# Si4703_Eval.net
KiCad netlist of a schematic drawn in EAGLE
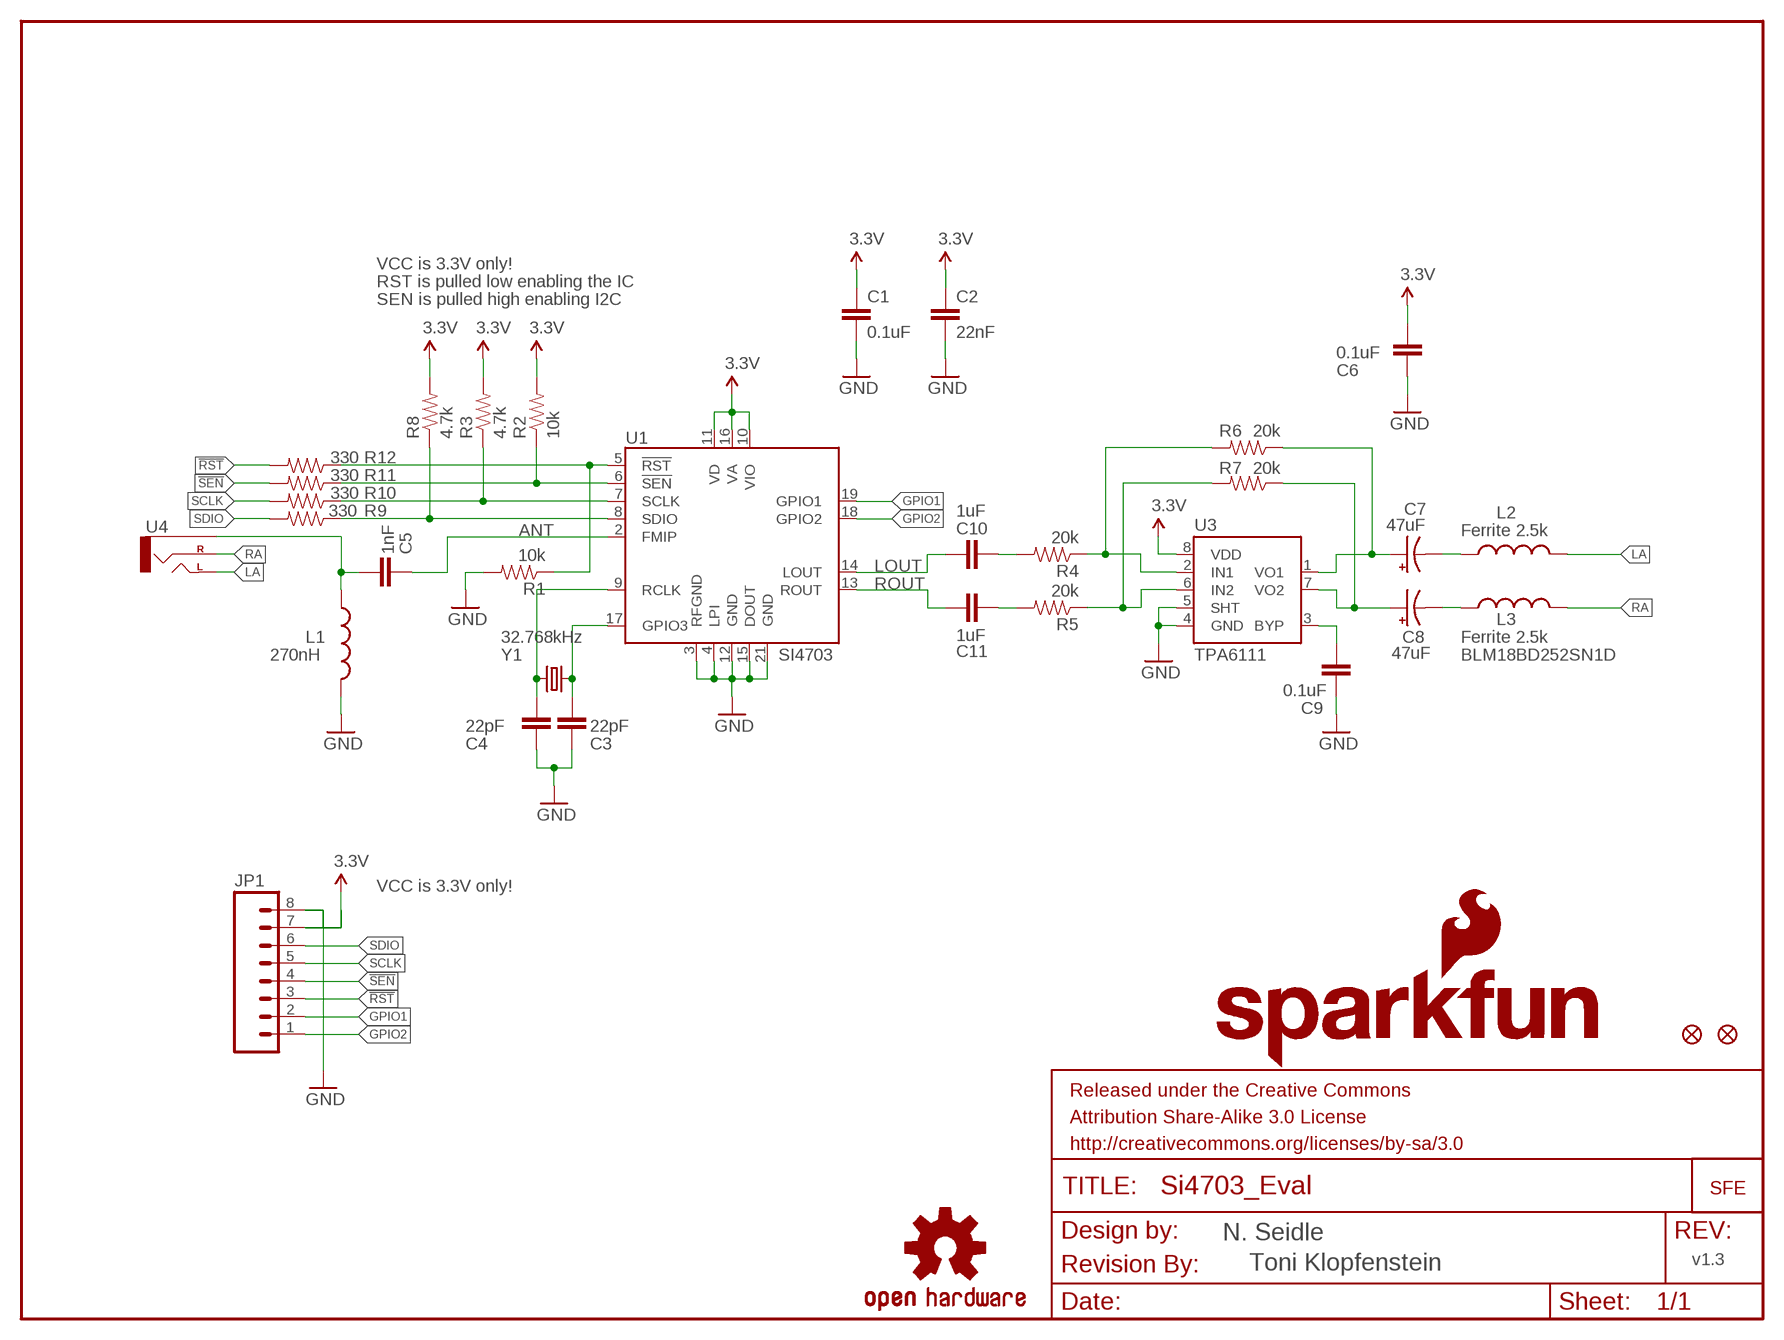
[diagram p0: schematic, sheet 1]

(export (version "E")
  (design (tool "Eeschema 10.0.6"))
  (components
    (comp (ref "C1")
      (value "0.1uF")
      (footprint "eagle-import:0603-CAP")
      (libsource (lib "eagle-import") (part "0.1UF-25V(+80/-20%)(0603)"))
    )
    (comp (ref "C2")
      (value "22nF")
      (footprint "eagle-import:0603-CAP")
      (libsource (lib "eagle-import") (part "22NF/22,000PF-50V-10%(0603)"))
    )
    (comp (ref "C3")
      (value "22pF")
      (footprint "eagle-import:0603-CAP")
      (libsource (lib "eagle-import") (part "22PF-50V-5%(0603)"))
    )
    (comp (ref "C4")
      (value "22pF")
      (footprint "eagle-import:0603-CAP")
      (libsource (lib "eagle-import") (part "22PF-50V-5%(0603)"))
    )
    (comp (ref "C5")
      (value "1nF")
      (footprint "eagle-import:0603-CAP")
      (libsource (lib "eagle-import") (part "1NF/1000PF-50V-10%(0603)"))
    )
    (comp (ref "C6")
      (value "0.1uF")
      (footprint "eagle-import:0603-CAP")
      (libsource (lib "eagle-import") (part "0.1UF-25V(+80/-20%)(0603)"))
    )
    (comp (ref "C7")
      (value "47uF")
      (footprint "eagle-import:EIA3528")
      (libsource (lib "eagle-import") (part "47UF-TANT"))
    )
    (comp (ref "C8")
      (value "47uF")
      (footprint "eagle-import:EIA3528")
      (libsource (lib "eagle-import") (part "47UF-TANT"))
    )
    (comp (ref "C9")
      (value "0.1uF")
      (footprint "eagle-import:0603-CAP")
      (libsource (lib "eagle-import") (part "0.1UF-25V(+80/-20%)(0603)"))
    )
    (comp (ref "C10")
      (value "1uF")
      (footprint "eagle-import:0603-CAP")
      (libsource (lib "eagle-import") (part "1.0UF-16V-10%(0603)"))
    )
    (comp (ref "C11")
      (value "1uF")
      (footprint "eagle-import:0603-CAP")
      (libsource (lib "eagle-import") (part "1.0UF-16V-10%(0603)"))
    )
    (comp (ref "FRAME2")
      (value "FRAME-LETTER")
      (footprint "eagle-import:CREATIVE_COMMONS")
      (libsource (lib "eagle-import") (part "FRAME-LETTER"))
    )
    (comp (ref "JP1")
      (value "M08")
      (footprint "eagle-import:1X08")
      (libsource (lib "eagle-import") (part "M08"))
    )
    (comp (ref "JP3")
      (value "LOGO-SFESK")
      (footprint "eagle-import:SFE-LOGO-FLAME")
      (libsource (lib "eagle-import") (part "LOGO-SFESK"))
    )
    (comp (ref "JP4")
      (value "FIDUCIAL1X2")
      (footprint "eagle-import:FIDUCIAL-1X2")
      (libsource (lib "eagle-import") (part "FIDUCIAL1X2"))
    )
    (comp (ref "JP5")
      (value "FIDUCIAL1X2")
      (footprint "eagle-import:FIDUCIAL-1X2")
      (libsource (lib "eagle-import") (part "FIDUCIAL1X2"))
    )
    (comp (ref "L1")
      (value "270nH")
      (footprint "eagle-import:0603")
      (libsource (lib "eagle-import") (part "INDUCTOR0603"))
    )
    (comp (ref "L2")
      (value "Ferrite 2.5k")
      (footprint "eagle-import:0603")
      (libsource (lib "eagle-import") (part "INDUCTOR0603"))
    )
    (comp (ref "L3")
      (value "Ferrite 2.5k")
      (footprint "eagle-import:0603")
      (libsource (lib "eagle-import") (part "INDUCTOR0603"))
    )
    (comp (ref "LOGO1")
      (value "SFE_LOGO_NAME_FLAME.1_INCH")
      (footprint "eagle-import:SFE_LOGO_NAME_FLAME_.1")
      (libsource (lib "eagle-import") (part "SFE_LOGO_NAME_FLAME.1_INCH"))
    )
    (comp (ref "LOGO2")
      (value "OSHW-LOGOS")
      (footprint "eagle-import:OSHW-LOGO-S")
      (libsource (lib "eagle-import") (part "OSHW-LOGOS"))
    )
    (comp (ref "R1")
      (value "10k")
      (footprint "eagle-import:0603-RES")
      (libsource (lib "eagle-import") (part "10KOHM1/10W1%(0603)0603"))
    )
    (comp (ref "R2")
      (value "10k")
      (footprint "eagle-import:0603-RES")
      (libsource (lib "eagle-import") (part "10KOHM1/10W1%(0603)0603"))
    )
    (comp (ref "R3")
      (value "4.7k")
      (footprint "eagle-import:0603")
      (libsource (lib "eagle-import") (part "4.7KOHM1/10W1%(0603)"))
    )
    (comp (ref "R4")
      (value "20k")
      (footprint "eagle-import:0603-RES")
      (libsource (lib "eagle-import") (part "20KOHM1/10W1%(0603)"))
    )
    (comp (ref "R5")
      (value "20k")
      (footprint "eagle-import:0603-RES")
      (libsource (lib "eagle-import") (part "20KOHM1/10W1%(0603)"))
    )
    (comp (ref "R6")
      (value "20k")
      (footprint "eagle-import:0603-RES")
      (libsource (lib "eagle-import") (part "20KOHM1/10W1%(0603)"))
    )
    (comp (ref "R7")
      (value "20k")
      (footprint "eagle-import:0603-RES")
      (libsource (lib "eagle-import") (part "20KOHM1/10W1%(0603)"))
    )
    (comp (ref "R8")
      (value "4.7k")
      (footprint "eagle-import:0603")
      (libsource (lib "eagle-import") (part "4.7KOHM1/10W1%(0603)"))
    )
    (comp (ref "R9")
      (value "330")
      (footprint "eagle-import:0603-RES")
      (libsource (lib "eagle-import") (part "330OHM1/10W1%(0603)"))
    )
    (comp (ref "R10")
      (value "330")
      (footprint "eagle-import:0603-RES")
      (libsource (lib "eagle-import") (part "330OHM1/10W1%(0603)"))
    )
    (comp (ref "R11")
      (value "330")
      (footprint "eagle-import:0603-RES")
      (libsource (lib "eagle-import") (part "330OHM1/10W1%(0603)"))
    )
    (comp (ref "R12")
      (value "330")
      (footprint "eagle-import:0603-RES")
      (libsource (lib "eagle-import") (part "330OHM1/10W1%(0603)"))
    )
    (comp (ref "U$1")
      (value "REVISION")
      (footprint "eagle-import:REVISION")
      (libsource (lib "eagle-import") (part "REVISION"))
    )
    (comp (ref "U1")
      (value "SI4703")
      (footprint "eagle-import:SI470X")
      (libsource (lib "eagle-import") (part "SI470X"))
    )
    (comp (ref "U3")
      (value "TPA6111")
      (footprint "eagle-import:SO08-TIGHT")
      (libsource (lib "eagle-import") (part "TPA6111SMD-T"))
    )
    (comp (ref "U4")
      (value "AUDIO-JACKSMD2")
      (footprint "eagle-import:AUDIO-JACK-3.5MM-SMD")
      (libsource (lib "eagle-import") (part "AUDIO-JACKSMD2"))
    )
    (comp (ref "Y1")
      (value "32.768kHz")
      (footprint "eagle-import:CRYSTAL-32KHZ-SMD")
      (libsource (lib "eagle-import") (part "CRYSTAL32-SMD"))
    )
  )
  (nets
    (net (code "1") (name "/ANT") (class "Default")
      (node (ref "C5") (pin "1") (pinfunction "1_1") (pintype "passive"))
      (node (ref "U1") (pin "2") (pinfunction "FMIP_2") (pintype "bidirectional"))
    )
    (net (code "2") (name "/LOUT") (class "Default")
      (node (ref "C10") (pin "1") (pinfunction "1_1") (pintype "passive"))
      (node (ref "U1") (pin "14") (pinfunction "LOUT_14") (pintype "bidirectional"))
    )
    (net (code "3") (name "/ROUT") (class "Default")
      (node (ref "C11") (pin "1") (pinfunction "1_1") (pintype "passive"))
      (node (ref "U1") (pin "13") (pinfunction "ROUT_13") (pintype "bidirectional"))
    )
    (net (code "4") (name "/~{RST}") (class "Default")
      (node (ref "JP1") (pin "3") (pinfunction "3_3") (pintype "passive"))
      (node (ref "R12") (pin "2") (pinfunction "2_2") (pintype "passive"))
    )
    (net (code "5") (name "/~{SEN}") (class "Default")
      (node (ref "JP1") (pin "4") (pinfunction "4_4") (pintype "passive"))
      (node (ref "R11") (pin "2") (pinfunction "2_2") (pintype "passive"))
    )
    (net (code "6") (name "3.3V") (class "Default")
      (node (ref "C1") (pin "1") (pinfunction "1_1") (pintype "passive"))
      (node (ref "C2") (pin "1") (pinfunction "1_1") (pintype "passive"))
      (node (ref "C6") (pin "2") (pinfunction "2_2") (pintype "passive"))
      (node (ref "JP1") (pin "7") (pinfunction "7_7") (pintype "passive"))
      (node (ref "R2") (pin "2") (pinfunction "2_2") (pintype "passive"))
      (node (ref "R3") (pin "2") (pinfunction "2_2") (pintype "passive"))
      (node (ref "R8") (pin "2") (pinfunction "2_2") (pintype "passive"))
      (node (ref "U1") (pin "10") (pinfunction "VIO_10") (pintype "bidirectional"))
      (node (ref "U1") (pin "11") (pinfunction "VD_11") (pintype "bidirectional"))
      (node (ref "U1") (pin "16") (pinfunction "VA_16") (pintype "bidirectional"))
      (node (ref "U3") (pin "8") (pinfunction "VDD_8") (pintype "bidirectional"))
    )
    (net (code "7") (name "GND") (class "Default")
      (node (ref "C1") (pin "2") (pinfunction "2_2") (pintype "passive"))
      (node (ref "C2") (pin "2") (pinfunction "2_2") (pintype "passive"))
      (node (ref "C3") (pin "1") (pinfunction "1_1") (pintype "passive"))
      (node (ref "C4") (pin "1") (pinfunction "1_1") (pintype "passive"))
      (node (ref "C6") (pin "1") (pinfunction "1_1") (pintype "passive"))
      (node (ref "C9") (pin "2") (pinfunction "2_2") (pintype "passive"))
      (node (ref "JP1") (pin "8") (pinfunction "8_8") (pintype "passive"))
      (node (ref "L1") (pin "2") (pinfunction "2_2") (pintype "passive"))
      (node (ref "R1") (pin "2") (pinfunction "2_2") (pintype "passive"))
      (node (ref "U1") (pin "12") (pinfunction "GND_12") (pintype "bidirectional"))
      (node (ref "U1") (pin "15") (pinfunction "DOUT_15") (pintype "bidirectional"))
      (node (ref "U1") (pin "21") (pinfunction "GND_21") (pintype "bidirectional"))
      (node (ref "U1") (pin "3") (pinfunction "RFGND_3") (pintype "bidirectional"))
      (node (ref "U1") (pin "4") (pinfunction "LPI_4") (pintype "bidirectional"))
      (node (ref "U3") (pin "4") (pinfunction "GND_4") (pintype "bidirectional"))
      (node (ref "U3") (pin "5") (pinfunction "SHT_5") (pintype "bidirectional"))
    )
    (net (code "8") (name "GPIO1") (class "Default")
      (node (ref "JP1") (pin "2") (pinfunction "2_2") (pintype "passive"))
      (node (ref "U1") (pin "19") (pinfunction "GPIO1_19") (pintype "bidirectional"))
    )
    (net (code "9") (name "GPIO2") (class "Default")
      (node (ref "JP1") (pin "1") (pinfunction "1_1") (pintype "passive"))
      (node (ref "U1") (pin "18") (pinfunction "GPIO2_18") (pintype "bidirectional"))
    )
    (net (code "10") (name "LA") (class "Default")
      (node (ref "L2") (pin "2") (pinfunction "2_2") (pintype "passive"))
      (node (ref "U4") (pin "TIP") (pinfunction "LEFT_TIP") (pintype "bidirectional"))
    )
    (net (code "11") (name "Net-(C5-Pad2)") (class "Default")
      (node (ref "C5") (pin "2") (pinfunction "2_2") (pintype "passive"))
      (node (ref "L1") (pin "1") (pinfunction "1_1") (pintype "passive"))
      (node (ref "U4") (pin "SLEEVE") (pinfunction "SLEEVE_SLEEVE") (pintype "bidirectional"))
    )
    (net (code "12") (name "Net-(C7-+)") (class "Default")
      (node (ref "C7") (pin "A") (pinfunction "+_A") (pintype "passive"))
      (node (ref "R6") (pin "1") (pinfunction "1_1") (pintype "passive"))
      (node (ref "U3") (pin "1") (pinfunction "VO1_1") (pintype "bidirectional"))
    )
    (net (code "13") (name "Net-(C7--)") (class "Default")
      (node (ref "C7") (pin "C") (pinfunction "-_C") (pintype "passive"))
      (node (ref "L2") (pin "1") (pinfunction "1_1") (pintype "passive"))
    )
    (net (code "14") (name "Net-(C8-+)") (class "Default")
      (node (ref "C8") (pin "A") (pinfunction "+_A") (pintype "passive"))
      (node (ref "R7") (pin "1") (pinfunction "1_1") (pintype "passive"))
      (node (ref "U3") (pin "7") (pinfunction "VO2_7") (pintype "bidirectional"))
    )
    (net (code "15") (name "Net-(C8--)") (class "Default")
      (node (ref "C8") (pin "C") (pinfunction "-_C") (pintype "passive"))
      (node (ref "L3") (pin "1") (pinfunction "1_1") (pintype "passive"))
    )
    (net (code "16") (name "Net-(C10-Pad2)") (class "Default")
      (node (ref "C10") (pin "2") (pinfunction "2_2") (pintype "passive"))
      (node (ref "R4") (pin "2") (pinfunction "2_2") (pintype "passive"))
    )
    (net (code "17") (name "Net-(C11-Pad2)") (class "Default")
      (node (ref "C11") (pin "2") (pinfunction "2_2") (pintype "passive"))
      (node (ref "R5") (pin "2") (pinfunction "2_2") (pintype "passive"))
    )
    (net (code "18") (name "Net-(U1-GPIO3)") (class "Default")
      (node (ref "C3") (pin "2") (pinfunction "2_2") (pintype "passive"))
      (node (ref "U1") (pin "17") (pinfunction "GPIO3_17") (pintype "bidirectional"))
      (node (ref "Y1") (pin "X1") (pinfunction "1_X1") (pintype "passive"))
    )
    (net (code "19") (name "Net-(U1-RCLK)") (class "Default")
      (node (ref "C4") (pin "2") (pinfunction "2_2") (pintype "passive"))
      (node (ref "U1") (pin "9") (pinfunction "RCLK_9") (pintype "bidirectional"))
      (node (ref "Y1") (pin "X2") (pinfunction "2_X2") (pintype "passive"))
    )
    (net (code "20") (name "Net-(U1-SCLK)") (class "Default")
      (node (ref "R10") (pin "1") (pinfunction "1_1") (pintype "passive"))
      (node (ref "R3") (pin "1") (pinfunction "1_1") (pintype "passive"))
      (node (ref "U1") (pin "7") (pinfunction "SCLK_7") (pintype "bidirectional"))
    )
    (net (code "21") (name "Net-(U1-SDIO)") (class "Default")
      (node (ref "R8") (pin "1") (pinfunction "1_1") (pintype "passive"))
      (node (ref "R9") (pin "1") (pinfunction "1_1") (pintype "passive"))
      (node (ref "U1") (pin "8") (pinfunction "SDIO_8") (pintype "bidirectional"))
    )
    (net (code "22") (name "Net-(U1-~{RST})") (class "Default")
      (node (ref "R1") (pin "1") (pinfunction "1_1") (pintype "passive"))
      (node (ref "R12") (pin "1") (pinfunction "1_1") (pintype "passive"))
      (node (ref "U1") (pin "5") (pinfunction "~{RST}_5") (pintype "bidirectional"))
    )
    (net (code "23") (name "Net-(U1-~{SEN})") (class "Default")
      (node (ref "R11") (pin "1") (pinfunction "1_1") (pintype "passive"))
      (node (ref "R2") (pin "1") (pinfunction "1_1") (pintype "passive"))
      (node (ref "U1") (pin "6") (pinfunction "~{SEN}_6") (pintype "bidirectional"))
    )
    (net (code "24") (name "Net-(U3-BYP)") (class "Default")
      (node (ref "C9") (pin "1") (pinfunction "1_1") (pintype "passive"))
      (node (ref "U3") (pin "3") (pinfunction "BYP_3") (pintype "bidirectional"))
    )
    (net (code "25") (name "Net-(U3-IN1)") (class "Default")
      (node (ref "R4") (pin "1") (pinfunction "1_1") (pintype "passive"))
      (node (ref "R6") (pin "2") (pinfunction "2_2") (pintype "passive"))
      (node (ref "U3") (pin "2") (pinfunction "IN1_2") (pintype "bidirectional"))
    )
    (net (code "26") (name "Net-(U3-IN2)") (class "Default")
      (node (ref "R5") (pin "1") (pinfunction "1_1") (pintype "passive"))
      (node (ref "R7") (pin "2") (pinfunction "2_2") (pintype "passive"))
      (node (ref "U3") (pin "6") (pinfunction "IN2_6") (pintype "bidirectional"))
    )
    (net (code "27") (name "RA") (class "Default")
      (node (ref "L3") (pin "2") (pinfunction "2_2") (pintype "passive"))
      (node (ref "U4") (pin "RING") (pinfunction "RIGHT_RING") (pintype "bidirectional"))
    )
    (net (code "28") (name "SCLK") (class "Default")
      (node (ref "JP1") (pin "5") (pinfunction "5_5") (pintype "passive"))
      (node (ref "R10") (pin "2") (pinfunction "2_2") (pintype "passive"))
    )
    (net (code "29") (name "SDIO") (class "Default")
      (node (ref "JP1") (pin "6") (pinfunction "6_6") (pintype "passive"))
      (node (ref "R9") (pin "2") (pinfunction "2_2") (pintype "passive"))
    )
  )
)
